# DimmingExpansion.net
KiCad netlist of a schematic drawn in EAGLE
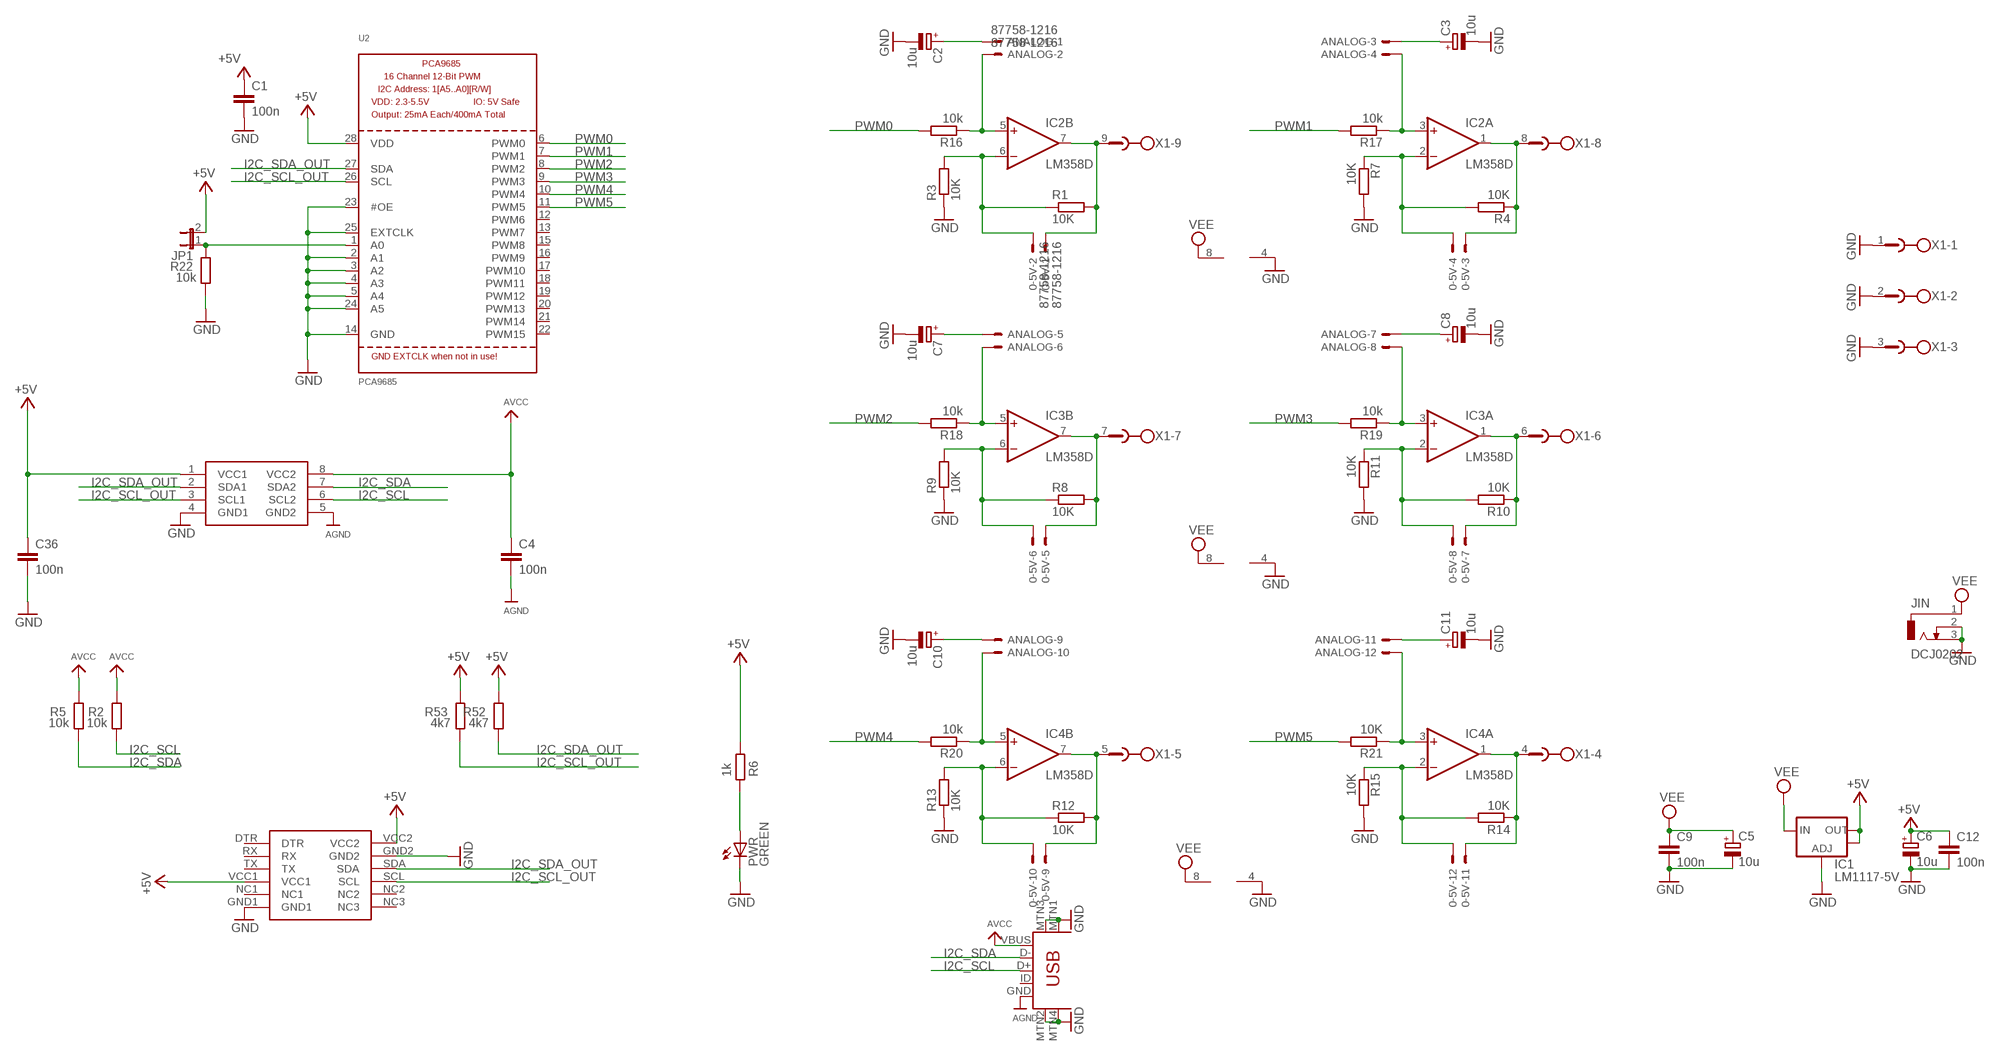
[diagram p0: schematic, sheet 1]

(export (version "E")
  (design (tool "Eeschema 10.0.6"))
  (components
    (comp (ref "0-5V")
      (value "87758-1216")
      (footprint "eagle-import:87758-1216")
      (libsource (lib "eagle-import") (part "87758-1216"))
    )
    (comp (ref "ANALOG")
      (value "87758-1216")
      (footprint "eagle-import:87758-1216")
      (libsource (lib "eagle-import") (part "87758-1216"))
    )
    (comp (ref "C1")
      (value "100n")
      (footprint "eagle-import:C0805")
      (libsource (lib "eagle-import") (part "C-EUC0805"))
    )
    (comp (ref "C2")
      (value "10u")
      (footprint "eagle-import:A_3216-18W")
      (libsource (lib "eagle-import") (part "CPOL-EUA/3216-18W"))
    )
    (comp (ref "C3")
      (value "10u")
      (footprint "eagle-import:A_3216-18W")
      (libsource (lib "eagle-import") (part "CPOL-EUA/3216-18W"))
    )
    (comp (ref "C4")
      (value "100n")
      (footprint "eagle-import:C0805")
      (libsource (lib "eagle-import") (part "C-EUC0805"))
    )
    (comp (ref "C5")
      (value "10u")
      (footprint "eagle-import:A_3216-18W")
      (libsource (lib "eagle-import") (part "CPOL-EUA/3216-18W"))
    )
    (comp (ref "C6")
      (value "10u")
      (footprint "eagle-import:A_3216-18W")
      (libsource (lib "eagle-import") (part "CPOL-EUA/3216-18W"))
    )
    (comp (ref "C7")
      (value "10u")
      (footprint "eagle-import:A_3216-18W")
      (libsource (lib "eagle-import") (part "CPOL-EUA/3216-18W"))
    )
    (comp (ref "C8")
      (value "10u")
      (footprint "eagle-import:A_3216-18W")
      (libsource (lib "eagle-import") (part "CPOL-EUA/3216-18W"))
    )
    (comp (ref "C9")
      (value "100n")
      (footprint "eagle-import:C0805")
      (libsource (lib "eagle-import") (part "C-EUC0805"))
    )
    (comp (ref "C10")
      (value "10u")
      (footprint "eagle-import:A_3216-18W")
      (libsource (lib "eagle-import") (part "CPOL-EUA/3216-18W"))
    )
    (comp (ref "C11")
      (value "10u")
      (footprint "eagle-import:A_3216-18W")
      (libsource (lib "eagle-import") (part "CPOL-EUA/3216-18W"))
    )
    (comp (ref "C12")
      (value "100n")
      (footprint "eagle-import:C0805")
      (libsource (lib "eagle-import") (part "C-EUC0805"))
    )
    (comp (ref "C36")
      (value "100n")
      (footprint "eagle-import:C0805")
      (libsource (lib "eagle-import") (part "C-EUC0805"))
    )
    (comp (ref "IC1")
      (value "LM1117-5V")
      (footprint "eagle-import:SOT223")
      (libsource (lib "eagle-import") (part "V_REG_LM1117SOT223"))
    )
    (comp (ref "IC2")
      (value "LM358D")
      (footprint "eagle-import:SO08")
      (libsource (lib "eagle-import") (part "LM358D"))
    )
    (comp (ref "IC3")
      (value "LM358D")
      (footprint "eagle-import:SO08")
      (libsource (lib "eagle-import") (part "LM358D"))
    )
    (comp (ref "IC4")
      (value "LM358D")
      (footprint "eagle-import:SO08")
      (libsource (lib "eagle-import") (part "LM358D"))
    )
    (comp (ref "JIN")
      (value "DCJ0202")
      (footprint "eagle-import:DCJ0202")
      (libsource (lib "eagle-import") (part "DCJ0202"))
    )
    (comp (ref "JP1")
      (value "JP1E")
      (footprint "eagle-import:JP1")
      (libsource (lib "eagle-import") (part "JP1E"))
    )
    (comp (ref "PWR")
      (value "GREEN")
      (footprint "eagle-import:LED3MM")
      (libsource (lib "eagle-import") (part "LED3MM"))
    )
    (comp (ref "R1")
      (value "10K")
      (footprint "eagle-import:R0805")
      (libsource (lib "eagle-import") (part "R-EU_R0805"))
    )
    (comp (ref "R2")
      (value "10k")
      (footprint "eagle-import:R0805")
      (libsource (lib "eagle-import") (part "R-EU_R0805"))
    )
    (comp (ref "R3")
      (value "10K")
      (footprint "eagle-import:R0805")
      (libsource (lib "eagle-import") (part "R-EU_R0805"))
    )
    (comp (ref "R4")
      (value "10K")
      (footprint "eagle-import:R0805")
      (libsource (lib "eagle-import") (part "R-EU_R0805"))
    )
    (comp (ref "R5")
      (value "10k")
      (footprint "eagle-import:R0805")
      (libsource (lib "eagle-import") (part "R-EU_R0805"))
    )
    (comp (ref "R6")
      (value "1k")
      (footprint "eagle-import:R0805")
      (libsource (lib "eagle-import") (part "R-EU_R0805"))
    )
    (comp (ref "R7")
      (value "10K")
      (footprint "eagle-import:R0805")
      (libsource (lib "eagle-import") (part "R-EU_R0805"))
    )
    (comp (ref "R8")
      (value "10K")
      (footprint "eagle-import:R0805")
      (libsource (lib "eagle-import") (part "R-EU_R0805"))
    )
    (comp (ref "R9")
      (value "10K")
      (footprint "eagle-import:R0805")
      (libsource (lib "eagle-import") (part "R-EU_R0805"))
    )
    (comp (ref "R10")
      (value "10K")
      (footprint "eagle-import:R0805")
      (libsource (lib "eagle-import") (part "R-EU_R0805"))
    )
    (comp (ref "R11")
      (value "10K")
      (footprint "eagle-import:R0805")
      (libsource (lib "eagle-import") (part "R-EU_R0805"))
    )
    (comp (ref "R12")
      (value "10K")
      (footprint "eagle-import:R0805")
      (libsource (lib "eagle-import") (part "R-EU_R0805"))
    )
    (comp (ref "R13")
      (value "10K")
      (footprint "eagle-import:R0805")
      (libsource (lib "eagle-import") (part "R-EU_R0805"))
    )
    (comp (ref "R14")
      (value "10K")
      (footprint "eagle-import:R0805")
      (libsource (lib "eagle-import") (part "R-EU_R0805"))
    )
    (comp (ref "R15")
      (value "10K")
      (footprint "eagle-import:R0805")
      (libsource (lib "eagle-import") (part "R-EU_R0805"))
    )
    (comp (ref "R16")
      (value "10k")
      (footprint "eagle-import:R0805")
      (libsource (lib "eagle-import") (part "R-EU_R0805"))
    )
    (comp (ref "R17")
      (value "10k")
      (footprint "eagle-import:R0805")
      (libsource (lib "eagle-import") (part "R-EU_R0805"))
    )
    (comp (ref "R18")
      (value "10k")
      (footprint "eagle-import:R0805")
      (libsource (lib "eagle-import") (part "R-EU_R0805"))
    )
    (comp (ref "R19")
      (value "10k")
      (footprint "eagle-import:R0805")
      (libsource (lib "eagle-import") (part "R-EU_R0805"))
    )
    (comp (ref "R20")
      (value "10k")
      (footprint "eagle-import:R0805")
      (libsource (lib "eagle-import") (part "R-EU_R0805"))
    )
    (comp (ref "R21")
      (value "10K")
      (footprint "eagle-import:R0805")
      (libsource (lib "eagle-import") (part "R-EU_R0805"))
    )
    (comp (ref "R22")
      (value "10k")
      (footprint "eagle-import:R0805")
      (libsource (lib "eagle-import") (part "R-EU_R0805"))
    )
    (comp (ref "R52")
      (value "4k7")
      (footprint "eagle-import:R0805")
      (libsource (lib "eagle-import") (part "R-EU_R0805"))
    )
    (comp (ref "R53")
      (value "4k7")
      (footprint "eagle-import:R0805")
      (libsource (lib "eagle-import") (part "R-EU_R0805"))
    )
    (comp (ref "U$2")
      (value "RANET_RECEIVERRANET")
      (footprint "eagle-import:RANET_RECEIVER")
      (libsource (lib "eagle-import") (part "RANET_RECEIVERRANET"))
    )
    (comp (ref "U$11")
      (value "USB-MINIB-5PIN")
      (footprint "eagle-import:USB-MINIB")
      (libsource (lib "eagle-import") (part "USB-MINIB-5PIN"))
    )
    (comp (ref "U1")
      (value "ADUM1250")
      (footprint "eagle-import:SO08")
      (libsource (lib "eagle-import") (part "ADUM1250"))
    )
    (comp (ref "U2")
      (value "PCA9685")
      (footprint "eagle-import:TSSOP28")
      (libsource (lib "eagle-import") (part "PCA9685"))
    )
    (comp (ref "X1")
      (value "MSTBV9")
      (footprint "eagle-import:MSTBV9")
      (libsource (lib "eagle-import") (part "MSTBV9"))
    )
  )
  (nets
    (net (code "1") (name "+5V") (class "Default")
      (node (ref "C1") (pin "1") (pinfunction "1_1") (pintype "passive"))
      (node (ref "C12") (pin "1") (pinfunction "1_1") (pintype "passive"))
      (node (ref "C36") (pin "1") (pinfunction "1_1") (pintype "passive"))
      (node (ref "C6") (pin "+") (pinfunction "+_+") (pintype "passive"))
      (node (ref "IC1") (pin "2") (pinfunction "OUT_2") (pintype "output"))
      (node (ref "IC1") (pin "4") (pinfunction "OUT_4") (pintype "output"))
      (node (ref "JP1") (pin "2") (pinfunction "2_2") (pintype "passive"))
      (node (ref "R52") (pin "2") (pinfunction "2_2") (pintype "passive"))
      (node (ref "R53") (pin "2") (pinfunction "2_2") (pintype "passive"))
      (node (ref "R6") (pin "1") (pinfunction "1_1") (pintype "passive"))
      (node (ref "U$2") (pin "VCC1") (pinfunction "VCC1_VCC1") (pintype "bidirectional"))
      (node (ref "U$2") (pin "VCC2") (pinfunction "VCC2_VCC2") (pintype "bidirectional"))
      (node (ref "U1") (pin "1") (pinfunction "VCC1_1") (pintype "bidirectional"))
      (node (ref "U2") (pin "28") (pinfunction "VDD_28") (pintype "power_in"))
    )
    (net (code "2") (name "/I2C_SCL") (class "Default")
      (node (ref "R2") (pin "1") (pinfunction "1_1") (pintype "passive"))
      (node (ref "U$11") (pin "D+") (pinfunction "D+_D+") (pintype "bidirectional"))
      (node (ref "U1") (pin "6") (pinfunction "SCL2_6") (pintype "bidirectional"))
    )
    (net (code "3") (name "/I2C_SCL_OUT") (class "Default")
      (node (ref "R53") (pin "1") (pinfunction "1_1") (pintype "passive"))
      (node (ref "U$2") (pin "SCL") (pinfunction "SCL_SCL") (pintype "bidirectional"))
      (node (ref "U1") (pin "3") (pinfunction "SCL1_3") (pintype "bidirectional"))
      (node (ref "U2") (pin "26") (pinfunction "SCL_26") (pintype "bidirectional"))
    )
    (net (code "4") (name "/I2C_SDA") (class "Default")
      (node (ref "R5") (pin "1") (pinfunction "1_1") (pintype "passive"))
      (node (ref "U$11") (pin "D-") (pinfunction "D-_D-") (pintype "bidirectional"))
      (node (ref "U1") (pin "7") (pinfunction "SDA2_7") (pintype "bidirectional"))
    )
    (net (code "5") (name "/I2C_SDA_OUT") (class "Default")
      (node (ref "R52") (pin "1") (pinfunction "1_1") (pintype "passive"))
      (node (ref "U$2") (pin "SDA") (pinfunction "SDA_SDA") (pintype "bidirectional"))
      (node (ref "U1") (pin "2") (pinfunction "SDA1_2") (pintype "bidirectional"))
      (node (ref "U2") (pin "27") (pinfunction "SDA_27") (pintype "bidirectional"))
    )
    (net (code "6") (name "/PWM0") (class "Default")
      (node (ref "R16") (pin "2") (pinfunction "2_2") (pintype "passive"))
      (node (ref "U2") (pin "6") (pinfunction "PWM0_6") (pintype "output"))
    )
    (net (code "7") (name "/PWM1") (class "Default")
      (node (ref "R17") (pin "2") (pinfunction "2_2") (pintype "passive"))
      (node (ref "U2") (pin "7") (pinfunction "PWM1_7") (pintype "output"))
    )
    (net (code "8") (name "/PWM2") (class "Default")
      (node (ref "R18") (pin "2") (pinfunction "2_2") (pintype "passive"))
      (node (ref "U2") (pin "8") (pinfunction "PWM2_8") (pintype "output"))
    )
    (net (code "9") (name "/PWM3") (class "Default")
      (node (ref "R19") (pin "2") (pinfunction "2_2") (pintype "passive"))
      (node (ref "U2") (pin "9") (pinfunction "PWM3_9") (pintype "output"))
    )
    (net (code "10") (name "/PWM4") (class "Default")
      (node (ref "R20") (pin "2") (pinfunction "2_2") (pintype "passive"))
      (node (ref "U2") (pin "10") (pinfunction "PWM4_10") (pintype "output"))
    )
    (net (code "11") (name "/PWM5") (class "Default")
      (node (ref "R21") (pin "2") (pinfunction "2_2") (pintype "passive"))
      (node (ref "U2") (pin "11") (pinfunction "PWM5_11") (pintype "output"))
    )
    (net (code "12") (name "AGND") (class "Default")
      (node (ref "C4") (pin "2") (pinfunction "2_2") (pintype "passive"))
      (node (ref "U$11") (pin "GND") (pinfunction "GND_GND") (pintype "bidirectional"))
      (node (ref "U1") (pin "5") (pinfunction "GND2_5") (pintype "bidirectional"))
    )
    (net (code "13") (name "AVCC") (class "Default")
      (node (ref "C4") (pin "1") (pinfunction "1_1") (pintype "passive"))
      (node (ref "R2") (pin "2") (pinfunction "2_2") (pintype "passive"))
      (node (ref "R5") (pin "2") (pinfunction "2_2") (pintype "passive"))
      (node (ref "U$11") (pin "VBUS") (pinfunction "VBUS_VBUS") (pintype "bidirectional"))
      (node (ref "U1") (pin "8") (pinfunction "VCC2_8") (pintype "bidirectional"))
    )
    (net (code "14") (name "GND") (class "Default")
      (node (ref "C1") (pin "2") (pinfunction "2_2") (pintype "passive"))
      (node (ref "C10") (pin "-") (pinfunction "-_-") (pintype "passive"))
      (node (ref "C11") (pin "-") (pinfunction "-_-") (pintype "passive"))
      (node (ref "C12") (pin "2") (pinfunction "2_2") (pintype "passive"))
      (node (ref "C2") (pin "-") (pinfunction "-_-") (pintype "passive"))
      (node (ref "C3") (pin "-") (pinfunction "-_-") (pintype "passive"))
      (node (ref "C36") (pin "2") (pinfunction "2_2") (pintype "passive"))
      (node (ref "C5") (pin "-") (pinfunction "-_-") (pintype "passive"))
      (node (ref "C6") (pin "-") (pinfunction "-_-") (pintype "passive"))
      (node (ref "C7") (pin "-") (pinfunction "-_-") (pintype "passive"))
      (node (ref "C8") (pin "-") (pinfunction "-_-") (pintype "passive"))
      (node (ref "C9") (pin "2") (pinfunction "2_2") (pintype "passive"))
      (node (ref "IC1") (pin "1") (pinfunction "ADJ_1") (pintype "input"))
      (node (ref "IC2") (pin "4") (pinfunction "V-_4") (pintype "power_in"))
      (node (ref "IC3") (pin "4") (pinfunction "V-_4") (pintype "power_in"))
      (node (ref "IC4") (pin "4") (pinfunction "V-_4") (pintype "power_in"))
      (node (ref "JIN") (pin "2") (pinfunction "2_2") (pintype "passive"))
      (node (ref "JIN") (pin "3") (pinfunction "3_3") (pintype "passive"))
      (node (ref "PWR") (pin "K") (pinfunction "C_K") (pintype "passive"))
      (node (ref "R11") (pin "2") (pinfunction "2_2") (pintype "passive"))
      (node (ref "R13") (pin "1") (pinfunction "1_1") (pintype "passive"))
      (node (ref "R15") (pin "2") (pinfunction "2_2") (pintype "passive"))
      (node (ref "R22") (pin "1") (pinfunction "1_1") (pintype "passive"))
      (node (ref "R3") (pin "1") (pinfunction "1_1") (pintype "passive"))
      (node (ref "R7") (pin "2") (pinfunction "2_2") (pintype "passive"))
      (node (ref "R9") (pin "1") (pinfunction "1_1") (pintype "passive"))
      (node (ref "U$11") (pin "MTN1") (pinfunction "MTN2_MTN1") (pintype "bidirectional"))
      (node (ref "U$11") (pin "MTN2") (pinfunction "MTN3_MTN2") (pintype "bidirectional"))
      (node (ref "U$11") (pin "MTN3") (pinfunction "MTN1_MTN3") (pintype "bidirectional"))
      (node (ref "U$11") (pin "MTN4") (pinfunction "MTN4_MTN4") (pintype "bidirectional"))
      (node (ref "U$2") (pin "GND1") (pinfunction "GND1_GND1") (pintype "bidirectional"))
      (node (ref "U$2") (pin "GND2") (pinfunction "GND2_GND2") (pintype "bidirectional"))
      (node (ref "U1") (pin "4") (pinfunction "GND1_4") (pintype "bidirectional"))
      (node (ref "U2") (pin "14") (pinfunction "GND_14") (pintype "power_in"))
      (node (ref "U2") (pin "2") (pinfunction "A1_2") (pintype "bidirectional"))
      (node (ref "U2") (pin "23") (pinfunction "#OE_23") (pintype "input"))
      (node (ref "U2") (pin "24") (pinfunction "A5_24") (pintype "bidirectional"))
      (node (ref "U2") (pin "25") (pinfunction "EXTCLK_25") (pintype "input"))
      (node (ref "U2") (pin "3") (pinfunction "A2_3") (pintype "bidirectional"))
      (node (ref "U2") (pin "4") (pinfunction "A3_4") (pintype "bidirectional"))
      (node (ref "U2") (pin "5") (pinfunction "A4_5") (pintype "bidirectional"))
      (node (ref "X1") (pin "1") (pinfunction "1_1") (pintype "passive"))
      (node (ref "X1") (pin "2") (pinfunction "1_2") (pintype "passive"))
      (node (ref "X1") (pin "3") (pinfunction "1_3") (pintype "passive"))
    )
    (net (code "15") (name "Net-(0-5VA-S)") (class "Default")
      (node (ref "0-5V") (pin "1") (pinfunction "S_1") (pintype "passive"))
      (node (ref "IC2") (pin "7") (pinfunction "OUT_7") (pintype "output"))
      (node (ref "R1") (pin "2") (pinfunction "2_2") (pintype "passive"))
      (node (ref "X1") (pin "9") (pinfunction "1_9") (pintype "passive"))
    )
    (net (code "16") (name "Net-(0-5VB-S)") (class "Default")
      (node (ref "0-5V") (pin "10") (pinfunction "S_10") (pintype "passive"))
      (node (ref "IC4") (pin "6") (pinfunction "-IN_6") (pintype "input"))
      (node (ref "R12") (pin "1") (pinfunction "1_1") (pintype "passive"))
      (node (ref "R13") (pin "2") (pinfunction "2_2") (pintype "passive"))
    )
    (net (code "17") (name "Net-(0-5VC-S)") (class "Default")
      (node (ref "0-5V") (pin "11") (pinfunction "S_11") (pintype "passive"))
      (node (ref "IC4") (pin "1") (pinfunction "OUT_1") (pintype "output"))
      (node (ref "R14") (pin "1") (pinfunction "1_1") (pintype "passive"))
      (node (ref "X1") (pin "4") (pinfunction "1_4") (pintype "passive"))
    )
    (net (code "18") (name "Net-(0-5VD-S)") (class "Default")
      (node (ref "0-5V") (pin "12") (pinfunction "S_12") (pintype "passive"))
      (node (ref "IC4") (pin "2") (pinfunction "-IN_2") (pintype "input"))
      (node (ref "R14") (pin "2") (pinfunction "2_2") (pintype "passive"))
      (node (ref "R15") (pin "1") (pinfunction "1_1") (pintype "passive"))
    )
    (net (code "19") (name "Net-(0-5VE-S)") (class "Default")
      (node (ref "0-5V") (pin "2") (pinfunction "S_2") (pintype "passive"))
      (node (ref "IC2") (pin "6") (pinfunction "-IN_6") (pintype "input"))
      (node (ref "R1") (pin "1") (pinfunction "1_1") (pintype "passive"))
      (node (ref "R3") (pin "2") (pinfunction "2_2") (pintype "passive"))
    )
    (net (code "20") (name "Net-(0-5VF-S)") (class "Default")
      (node (ref "0-5V") (pin "3") (pinfunction "S_3") (pintype "passive"))
      (node (ref "IC2") (pin "1") (pinfunction "OUT_1") (pintype "output"))
      (node (ref "R4") (pin "1") (pinfunction "1_1") (pintype "passive"))
      (node (ref "X1") (pin "8") (pinfunction "1_8") (pintype "passive"))
    )
    (net (code "21") (name "Net-(0-5VG-S)") (class "Default")
      (node (ref "0-5V") (pin "4") (pinfunction "S_4") (pintype "passive"))
      (node (ref "IC2") (pin "2") (pinfunction "-IN_2") (pintype "input"))
      (node (ref "R4") (pin "2") (pinfunction "2_2") (pintype "passive"))
      (node (ref "R7") (pin "1") (pinfunction "1_1") (pintype "passive"))
    )
    (net (code "22") (name "Net-(0-5VH-S)") (class "Default")
      (node (ref "0-5V") (pin "5") (pinfunction "S_5") (pintype "passive"))
      (node (ref "IC3") (pin "7") (pinfunction "OUT_7") (pintype "output"))
      (node (ref "R8") (pin "2") (pinfunction "2_2") (pintype "passive"))
      (node (ref "X1") (pin "7") (pinfunction "1_7") (pintype "passive"))
    )
    (net (code "23") (name "Net-(0-5VI-S)") (class "Default")
      (node (ref "0-5V") (pin "6") (pinfunction "S_6") (pintype "passive"))
      (node (ref "IC3") (pin "6") (pinfunction "-IN_6") (pintype "input"))
      (node (ref "R8") (pin "1") (pinfunction "1_1") (pintype "passive"))
      (node (ref "R9") (pin "2") (pinfunction "2_2") (pintype "passive"))
    )
    (net (code "24") (name "Net-(0-5VJ-S)") (class "Default")
      (node (ref "0-5V") (pin "7") (pinfunction "S_7") (pintype "passive"))
      (node (ref "IC3") (pin "1") (pinfunction "OUT_1") (pintype "output"))
      (node (ref "R10") (pin "1") (pinfunction "1_1") (pintype "passive"))
      (node (ref "X1") (pin "6") (pinfunction "1_6") (pintype "passive"))
    )
    (net (code "25") (name "Net-(0-5VK-S)") (class "Default")
      (node (ref "0-5V") (pin "8") (pinfunction "S_8") (pintype "passive"))
      (node (ref "IC3") (pin "2") (pinfunction "-IN_2") (pintype "input"))
      (node (ref "R10") (pin "2") (pinfunction "2_2") (pintype "passive"))
      (node (ref "R11") (pin "1") (pinfunction "1_1") (pintype "passive"))
    )
    (net (code "26") (name "Net-(0-5VL-S)") (class "Default")
      (node (ref "0-5V") (pin "9") (pinfunction "S_9") (pintype "passive"))
      (node (ref "IC4") (pin "7") (pinfunction "OUT_7") (pintype "output"))
      (node (ref "R12") (pin "2") (pinfunction "2_2") (pintype "passive"))
      (node (ref "X1") (pin "5") (pinfunction "1_5") (pintype "passive"))
    )
    (net (code "27") (name "Net-(ANALOGA-S)") (class "Default")
      (node (ref "ANALOG") (pin "1") (pinfunction "S_1") (pintype "passive"))
      (node (ref "C2") (pin "+") (pinfunction "+_+") (pintype "passive"))
    )
    (net (code "28") (name "Net-(ANALOGB-S)") (class "Default")
      (node (ref "ANALOG") (pin "10") (pinfunction "S_10") (pintype "passive"))
      (node (ref "IC4") (pin "5") (pinfunction "+IN_5") (pintype "input"))
      (node (ref "R20") (pin "1") (pinfunction "1_1") (pintype "passive"))
    )
    (net (code "29") (name "Net-(ANALOGC-S)") (class "Default")
      (node (ref "ANALOG") (pin "11") (pinfunction "S_11") (pintype "passive"))
      (node (ref "C11") (pin "+") (pinfunction "+_+") (pintype "passive"))
    )
    (net (code "30") (name "Net-(ANALOGD-S)") (class "Default")
      (node (ref "ANALOG") (pin "12") (pinfunction "S_12") (pintype "passive"))
      (node (ref "IC4") (pin "3") (pinfunction "+IN_3") (pintype "input"))
      (node (ref "R21") (pin "1") (pinfunction "1_1") (pintype "passive"))
    )
    (net (code "31") (name "Net-(ANALOGE-S)") (class "Default")
      (node (ref "ANALOG") (pin "2") (pinfunction "S_2") (pintype "passive"))
      (node (ref "IC2") (pin "5") (pinfunction "+IN_5") (pintype "input"))
      (node (ref "R16") (pin "1") (pinfunction "1_1") (pintype "passive"))
    )
    (net (code "32") (name "Net-(ANALOGF-S)") (class "Default")
      (node (ref "ANALOG") (pin "3") (pinfunction "S_3") (pintype "passive"))
      (node (ref "C3") (pin "+") (pinfunction "+_+") (pintype "passive"))
    )
    (net (code "33") (name "Net-(ANALOGG-S)") (class "Default")
      (node (ref "ANALOG") (pin "4") (pinfunction "S_4") (pintype "passive"))
      (node (ref "IC2") (pin "3") (pinfunction "+IN_3") (pintype "input"))
      (node (ref "R17") (pin "1") (pinfunction "1_1") (pintype "passive"))
    )
    (net (code "34") (name "Net-(ANALOGH-S)") (class "Default")
      (node (ref "ANALOG") (pin "5") (pinfunction "S_5") (pintype "passive"))
      (node (ref "C7") (pin "+") (pinfunction "+_+") (pintype "passive"))
    )
    (net (code "35") (name "Net-(ANALOGI-S)") (class "Default")
      (node (ref "ANALOG") (pin "6") (pinfunction "S_6") (pintype "passive"))
      (node (ref "IC3") (pin "5") (pinfunction "+IN_5") (pintype "input"))
      (node (ref "R18") (pin "1") (pinfunction "1_1") (pintype "passive"))
    )
    (net (code "36") (name "Net-(ANALOGJ-S)") (class "Default")
      (node (ref "ANALOG") (pin "7") (pinfunction "S_7") (pintype "passive"))
      (node (ref "C8") (pin "+") (pinfunction "+_+") (pintype "passive"))
    )
    (net (code "37") (name "Net-(ANALOGK-S)") (class "Default")
      (node (ref "ANALOG") (pin "8") (pinfunction "S_8") (pintype "passive"))
      (node (ref "IC3") (pin "3") (pinfunction "+IN_3") (pintype "input"))
      (node (ref "R19") (pin "1") (pinfunction "1_1") (pintype "passive"))
    )
    (net (code "38") (name "Net-(ANALOGL-S)") (class "Default")
      (node (ref "ANALOG") (pin "9") (pinfunction "S_9") (pintype "passive"))
      (node (ref "C10") (pin "+") (pinfunction "+_+") (pintype "passive"))
    )
    (net (code "39") (name "Net-(PWR-PadA)") (class "Default")
      (node (ref "PWR") (pin "A") (pinfunction "A_A") (pintype "passive"))
      (node (ref "R6") (pin "2") (pinfunction "2_2") (pintype "passive"))
    )
    (net (code "40") (name "Net-(U2-A0)") (class "Default")
      (node (ref "JP1") (pin "1") (pinfunction "1_1") (pintype "passive"))
      (node (ref "R22") (pin "2") (pinfunction "2_2") (pintype "passive"))
      (node (ref "U2") (pin "1") (pinfunction "A0_1") (pintype "bidirectional"))
    )
    (net (code "41") (name "VEE") (class "Default")
      (node (ref "C5") (pin "+") (pinfunction "+_+") (pintype "passive"))
      (node (ref "C9") (pin "1") (pinfunction "1_1") (pintype "passive"))
      (node (ref "IC1") (pin "3") (pinfunction "IN_3") (pintype "input"))
      (node (ref "IC2") (pin "8") (pinfunction "V+_8") (pintype "power_in"))
      (node (ref "IC3") (pin "8") (pinfunction "V+_8") (pintype "power_in"))
      (node (ref "IC4") (pin "8") (pinfunction "V+_8") (pintype "power_in"))
      (node (ref "JIN") (pin "1") (pinfunction "1_1") (pintype "passive"))
    )
    (net (code "42") (name "unconnected-(U$2-PadDTR)") (class "Default")
      (node (ref "U$2") (pin "DTR") (pinfunction "DTR_DTR") (pintype "bidirectional"))
    )
    (net (code "43") (name "unconnected-(U$2-PadNC1)") (class "Default")
      (node (ref "U$2") (pin "NC1") (pinfunction "NC1_NC1") (pintype "bidirectional"))
    )
    (net (code "44") (name "unconnected-(U$2-PadNC2)") (class "Default")
      (node (ref "U$2") (pin "NC2") (pinfunction "NC2_NC2") (pintype "bidirectional"))
    )
    (net (code "45") (name "unconnected-(U$2-PadNC3)") (class "Default")
      (node (ref "U$2") (pin "NC3") (pinfunction "NC3_NC3") (pintype "bidirectional"))
    )
    (net (code "46") (name "unconnected-(U$2-PadRX)") (class "Default")
      (node (ref "U$2") (pin "RX") (pinfunction "RX_RX") (pintype "bidirectional"))
    )
    (net (code "47") (name "unconnected-(U$2-PadTX)") (class "Default")
      (node (ref "U$2") (pin "TX") (pinfunction "TX_TX") (pintype "bidirectional"))
    )
    (net (code "48") (name "unconnected-(U$11-PadID)") (class "Default")
      (node (ref "U$11") (pin "ID") (pinfunction "ID_ID") (pintype "bidirectional"))
    )
    (net (code "49") (name "unconnected-(U2-PWM6-Pad12)") (class "Default")
      (node (ref "U2") (pin "12") (pinfunction "PWM6_12") (pintype "output"))
    )
    (net (code "50") (name "unconnected-(U2-PWM7-Pad13)") (class "Default")
      (node (ref "U2") (pin "13") (pinfunction "PWM7_13") (pintype "output"))
    )
    (net (code "51") (name "unconnected-(U2-PWM8-Pad15)") (class "Default")
      (node (ref "U2") (pin "15") (pinfunction "PWM8_15") (pintype "output"))
    )
    (net (code "52") (name "unconnected-(U2-PWM9-Pad16)") (class "Default")
      (node (ref "U2") (pin "16") (pinfunction "PWM9_16") (pintype "output"))
    )
    (net (code "53") (name "unconnected-(U2-PWM10-Pad17)") (class "Default")
      (node (ref "U2") (pin "17") (pinfunction "PWM10_17") (pintype "output"))
    )
    (net (code "54") (name "unconnected-(U2-PWM11-Pad18)") (class "Default")
      (node (ref "U2") (pin "18") (pinfunction "PWM11_18") (pintype "output"))
    )
    (net (code "55") (name "unconnected-(U2-PWM12-Pad19)") (class "Default")
      (node (ref "U2") (pin "19") (pinfunction "PWM12_19") (pintype "output"))
    )
    (net (code "56") (name "unconnected-(U2-PWM13-Pad20)") (class "Default")
      (node (ref "U2") (pin "20") (pinfunction "PWM13_20") (pintype "output"))
    )
    (net (code "57") (name "unconnected-(U2-PWM14-Pad21)") (class "Default")
      (node (ref "U2") (pin "21") (pinfunction "PWM14_21") (pintype "output"))
    )
    (net (code "58") (name "unconnected-(U2-PWM15-Pad22)") (class "Default")
      (node (ref "U2") (pin "22") (pinfunction "PWM15_22") (pintype "output"))
    )
  )
)
